# 03-WIFI.net
KiCad netlist of a schematic drawn in Altium Designer
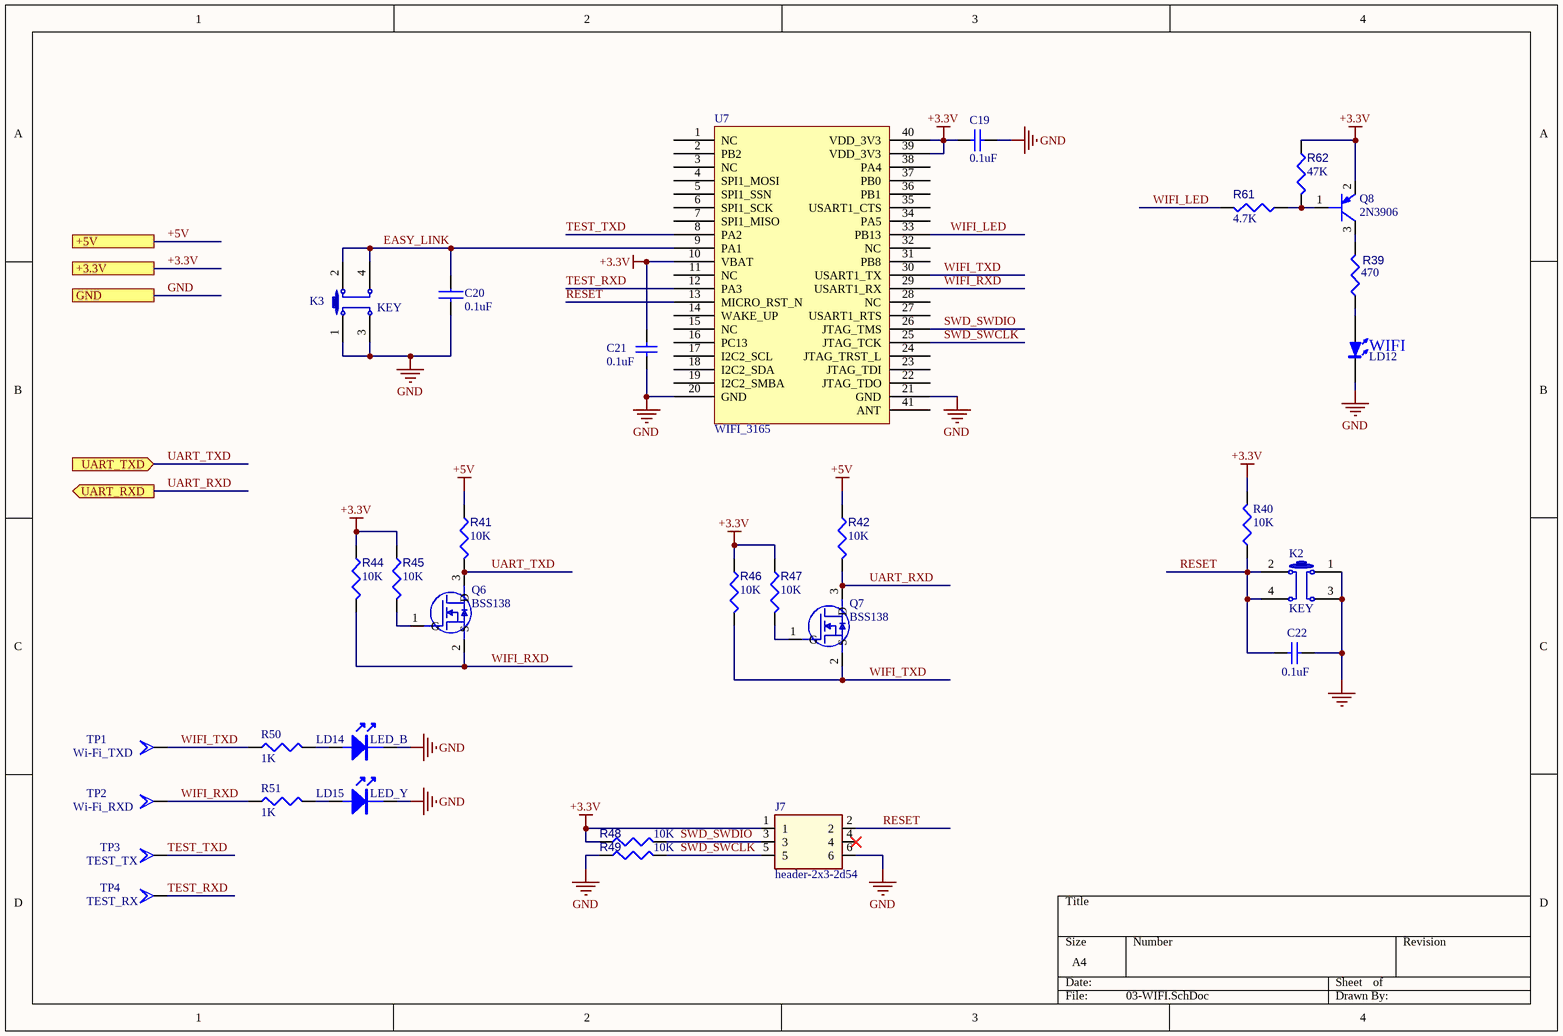
[diagram p0: 03-WIFI.SchDoc]

(export (version "E")
  (design (tool "Eeschema 10.0.6"))
  (components
    (comp (ref "C19")
      (value "0.1uF")
      (footprint "0805_C")
      (description "Capacitor")
      (fields (field (name "PUBLISHER") "Altium Limited"))
      (libsource (lib "EM_SENSOR_V3.01") (part "Cap Semi_1"))
    )
    (comp (ref "C20") (value "0.1uF") (footprint "0805_C") (libsource (lib "EM_SENSOR_V4.1") (part "CAP NP")))
    (comp (ref "C21")
      (value "0.1uF")
      (footprint "0805_C")
      (description "Capacitor")
      (fields (field (name "PUBLISHER") "Altium Limited"))
      (libsource (lib "EM_SENSOR_V2.03") (part "Cap Semi_1"))
    )
    (comp (ref "C22")
      (value "0.1uF")
      (footprint "0805_C")
      (description "Capacitor")
      (fields (field (name "PUBLISHER") "Altium Limited"))
      (libsource (lib "Miscellaneous Devices") (part "Cap"))
    )
    (comp (ref "J7")
      (value "header-2x3-2d54")
      (footprint "HT8550_FLASH_LOADER")
      (libsource (lib "EM_SENSOR_V3.01") (part "header-2x3-2d54"))
    )
    (comp (ref "K2") (value "KEY") (footprint "KEY_SMD5465") (libsource (lib "Schlib1") (part "KEY")))
    (comp (ref "K3") (value "KEY") (footprint "KEY_SMD5465") (libsource (lib "") (part "KEY_1")))
    (comp (ref "LD12")
      (value "WHITE")
      (footprint "LED1")
      (description "LED")
      (libsource (lib "*") (part "LED"))
    )
    (comp (ref "LD14")
      (value "LED_B")
      (footprint "LED_0805")
      (libsource (lib "EM_SENSOR_V2.03") (part "LED"))
    )
    (comp (ref "LD15")
      (value "LED_Y")
      (footprint "LED_0805")
      (libsource (lib "EM_SENSOR_V2.03") (part "LED"))
    )
    (comp (ref "Q6")
      (value "BSS138")
      (footprint "SOT23")
      (description "N-Channel Enhancement MOSFET")
      (libsource (lib "EP_MCB_V6.0") (part "N-Channel Enhancement MOSFET"))
    )
    (comp (ref "Q7")
      (value "BSS138")
      (footprint "SOT23")
      (description "N-Channel Enhancement MOSFET")
      (libsource (lib "EP_MCB_V6.0") (part "N-Channel Enhancement MOSFET"))
    )
    (comp (ref "Q8") (value "2N3906") (footprint "SOT23") (libsource (lib "MySchlib") (part "PNP")))
    (comp (ref "R39")
      (value "470")
      (footprint "0805_R")
      (description "Resistor")
      (fields (field (name "PUBLISHER") "Altium Limited"))
      (libsource (lib "EM_SENSOR_V3.01") (part "Res3"))
    )
    (comp (ref "R40")
      (value "10K")
      (footprint "0805_R")
      (description "Resistor")
      (fields (field (name "PUBLISHER") "Altium Limited"))
      (libsource (lib "Miscellaneous Devices") (part "Res3"))
    )
    (comp (ref "R41")
      (value "10K")
      (footprint "0805_R")
      (description "Resistor")
      (fields (field (name "PUBLISHER") "Altium Limited"))
      (libsource (lib "EP_MCB_V6.0") (part "Res3_3"))
    )
    (comp (ref "R42")
      (value "10K")
      (footprint "0805_R")
      (description "Resistor")
      (fields (field (name "PUBLISHER") "Altium Limited"))
      (libsource (lib "EP_MCB_V6.0") (part "Res3_3"))
    )
    (comp (ref "R44")
      (value "10K")
      (footprint "0805_R")
      (description "Resistor")
      (fields (field (name "PUBLISHER") "Altium Limited"))
      (libsource (lib "EP_MCB_V6.0") (part "Res3_3"))
    )
    (comp (ref "R45")
      (value "10K")
      (footprint "0805_R")
      (description "Resistor")
      (fields (field (name "PUBLISHER") "Altium Limited"))
      (libsource (lib "EP_MCB_V6.0") (part "Res3_3"))
    )
    (comp (ref "R46")
      (value "10K")
      (footprint "0805_R")
      (description "Resistor")
      (fields (field (name "PUBLISHER") "Altium Limited"))
      (libsource (lib "EP_MCB_V6.0") (part "Res3_3"))
    )
    (comp (ref "R47")
      (value "10K")
      (footprint "0805_R")
      (description "Resistor")
      (fields (field (name "PUBLISHER") "Altium Limited"))
      (libsource (lib "EP_MCB_V6.0") (part "Res3_3"))
    )
    (comp (ref "R48")
      (value "10K")
      (footprint "0805_R")
      (description "Resistor")
      (fields (field (name "PUBLISHER") "Altium Limited"))
      (libsource (lib "EM_SENSOR_V3.01") (part "Res3"))
    )
    (comp (ref "R49")
      (value "10K")
      (footprint "0805_R")
      (description "Resistor")
      (fields (field (name "PUBLISHER") "Altium Limited"))
      (libsource (lib "EM_SENSOR_V3.01") (part "Res3"))
    )
    (comp (ref "R50") (value "1K") (footprint "0805_R") (libsource (lib "EM_SENSOR_V2.01") (part "R")))
    (comp (ref "R51") (value "1K") (footprint "0805_R") (libsource (lib "EM_SENSOR_V2.01") (part "R")))
    (comp (ref "R61")
      (value "4.7K")
      (footprint "0805_R")
      (description "Resistor")
      (fields (field (name "PUBLISHER") "Altium Limited"))
      (libsource (lib "EM_SENSOR_V3.01") (part "Res3"))
    )
    (comp (ref "R62")
      (value "47K")
      (footprint "0805_R")
      (description "Resistor")
      (fields (field (name "PUBLISHER") "Altium Limited"))
      (libsource (lib "EM_SENSOR_V3.01") (part "Res3"))
    )
    (comp (ref "TP1")
      (value "Wi-Fi_TXD")
      (footprint "TP_60_30")
      (libsource (lib "EM_SENSOR_V2.01") (part "T POINT A"))
    )
    (comp (ref "TP2")
      (value "Wi-Fi_RXD")
      (footprint "TP_60_30")
      (libsource (lib "EM_SENSOR_V2.01") (part "T POINT A"))
    )
    (comp (ref "TP3")
      (value "TEST_TX")
      (footprint "TP_60_30")
      (libsource (lib "EM_SENSOR_V2.03") (part "T POINT A"))
    )
    (comp (ref "TP4")
      (value "TEST_RX")
      (footprint "TP_60_30")
      (libsource (lib "EM_SENSOR_V2.03") (part "T POINT A"))
    )
    (comp (ref "U7") (value "WIFI_3165") (footprint "EMW3165-P") (libsource (lib "*") (part "WIFI_3165")))
  )
  (nets
    (net (code "1") (name "+3.3V") (class "Default")
      (node (ref "C19") (pin "2") (pinfunction "2_2") (pintype "passive"))
      (node (ref "C21") (pin "2") (pinfunction "2_2") (pintype "passive"))
      (node (ref "J7") (pin "1") (pinfunction "1_1") (pintype "passive"))
      (node (ref "Q8") (pin "2") (pinfunction "EMITTER_2") (pintype "passive"))
      (node (ref "R40") (pin "2") (pinfunction "2_2") (pintype "passive"))
      (node (ref "R44") (pin "1") (pinfunction "1_1") (pintype "passive"))
      (node (ref "R45") (pin "1") (pinfunction "1_1") (pintype "passive"))
      (node (ref "R46") (pin "1") (pinfunction "1_1") (pintype "passive"))
      (node (ref "R47") (pin "1") (pinfunction "1_1") (pintype "passive"))
      (node (ref "R48") (pin "1") (pinfunction "1_1") (pintype "passive"))
      (node (ref "R62") (pin "1") (pinfunction "1_1") (pintype "passive"))
      (node (ref "U7") (pin "10") (pinfunction "VBAT_10") (pintype "passive"))
      (node (ref "U7") (pin "39") (pinfunction "VDD_3V3_39") (pintype "passive"))
      (node (ref "U7") (pin "40") (pinfunction "VDD_3V3_40") (pintype "passive"))
    )
    (net (code "2") (name "+5V") (class "Default")
      (node (ref "R41") (pin "1") (pinfunction "1_1") (pintype "passive"))
      (node (ref "R42") (pin "1") (pinfunction "1_1") (pintype "passive"))
    )
    (net (code "3") (name "/EASY_LINK") (class "Default")
      (node (ref "C20") (pin "1") (pinfunction "1_1") (pintype "passive"))
      (node (ref "K3") (pin "2") (pinfunction "2_2") (pintype "passive"))
      (node (ref "K3") (pin "4") (pinfunction "4_4") (pintype "passive"))
      (node (ref "U7") (pin "9") (pinfunction "PA1_9") (pintype "passive"))
    )
    (net (code "4") (name "/RESET") (class "Default")
      (node (ref "C22") (pin "2") (pinfunction "2_2") (pintype "passive"))
      (node (ref "J7") (pin "2") (pinfunction "2_2") (pintype "passive"))
      (node (ref "K2") (pin "2") (pinfunction "2_2") (pintype "passive"))
      (node (ref "K2") (pin "4") (pinfunction "4_4") (pintype "passive"))
      (node (ref "R40") (pin "1") (pinfunction "1_1") (pintype "passive"))
      (node (ref "U7") (pin "13") (pinfunction "MICRO_RST_N_13") (pintype "passive"))
    )
    (net (code "5") (name "/SWD_SWCLK") (class "Default")
      (node (ref "J7") (pin "5") (pinfunction "5_5") (pintype "passive"))
      (node (ref "R49") (pin "2") (pinfunction "2_2") (pintype "passive"))
      (node (ref "U7") (pin "25") (pinfunction "JTAG_TCK_25") (pintype "passive"))
    )
    (net (code "6") (name "/SWD_SWDIO") (class "Default")
      (node (ref "J7") (pin "3") (pinfunction "3_3") (pintype "passive"))
      (node (ref "R48") (pin "2") (pinfunction "2_2") (pintype "passive"))
      (node (ref "U7") (pin "26") (pinfunction "JTAG_TMS_26") (pintype "passive"))
    )
    (net (code "7") (name "/TEST_RXD") (class "Default")
      (node (ref "TP4") (pin "1") (pinfunction "TP_1") (pintype "passive"))
      (node (ref "U7") (pin "12") (pinfunction "PA3_12") (pintype "passive"))
    )
    (net (code "8") (name "/TEST_TXD") (class "Default")
      (node (ref "TP3") (pin "1") (pinfunction "TP_1") (pintype "passive"))
      (node (ref "U7") (pin "8") (pinfunction "PA2_8") (pintype "passive"))
    )
    (net (code "9") (name "/UART_RXD") (class "Default")
      (node (ref "Q7") (pin "3") (pinfunction "D_3") (pintype "passive"))
      (node (ref "R42") (pin "2") (pinfunction "2_2") (pintype "passive"))
    )
    (net (code "10") (name "/UART_TXD") (class "Default")
      (node (ref "Q6") (pin "3") (pinfunction "D_3") (pintype "passive"))
      (node (ref "R41") (pin "2") (pinfunction "2_2") (pintype "passive"))
    )
    (net (code "11") (name "/WIFI_LED") (class "Default")
      (node (ref "R61") (pin "2") (pinfunction "2_2") (pintype "passive"))
      (node (ref "U7") (pin "33") (pinfunction "PB13_33") (pintype "passive"))
    )
    (net (code "12") (name "/WIFI_RXD") (class "Default")
      (node (ref "Q6") (pin "2") (pinfunction "S_2") (pintype "passive"))
      (node (ref "R44") (pin "2") (pinfunction "2_2") (pintype "passive"))
      (node (ref "R51") (pin "1") (pinfunction "1_1") (pintype "passive"))
      (node (ref "TP2") (pin "1") (pinfunction "TP_1") (pintype "passive"))
      (node (ref "U7") (pin "29") (pinfunction "USART1_RX_29") (pintype "passive"))
    )
    (net (code "13") (name "/WIFI_TXD") (class "Default")
      (node (ref "Q7") (pin "2") (pinfunction "S_2") (pintype "passive"))
      (node (ref "R46") (pin "2") (pinfunction "2_2") (pintype "passive"))
      (node (ref "R50") (pin "1") (pinfunction "1_1") (pintype "passive"))
      (node (ref "TP1") (pin "1") (pinfunction "TP_1") (pintype "passive"))
      (node (ref "U7") (pin "30") (pinfunction "USART1_TX_30") (pintype "passive"))
    )
    (net (code "14") (name "GND") (class "Default")
      (node (ref "C19") (pin "1") (pinfunction "1_1") (pintype "passive"))
      (node (ref "C20") (pin "2") (pinfunction "2_2") (pintype "passive"))
      (node (ref "C21") (pin "1") (pinfunction "1_1") (pintype "passive"))
      (node (ref "C22") (pin "1") (pinfunction "1_1") (pintype "passive"))
      (node (ref "J7") (pin "6") (pinfunction "6_6") (pintype "passive"))
      (node (ref "K2") (pin "1") (pinfunction "1_1") (pintype "passive"))
      (node (ref "K2") (pin "3") (pinfunction "3_3") (pintype "passive"))
      (node (ref "K3") (pin "1") (pinfunction "1_1") (pintype "passive"))
      (node (ref "K3") (pin "3") (pinfunction "3_3") (pintype "passive"))
      (node (ref "LD12") (pin "K") (pinfunction "K_K") (pintype "passive"))
      (node (ref "LD14") (pin "K") (pinfunction "2_K") (pintype "passive"))
      (node (ref "LD15") (pin "K") (pinfunction "2_K") (pintype "passive"))
      (node (ref "R49") (pin "1") (pinfunction "1_1") (pintype "passive"))
      (node (ref "U7") (pin "20") (pinfunction "GND_20") (pintype "passive"))
      (node (ref "U7") (pin "21") (pinfunction "GND_21") (pintype "passive"))
    )
    (net (code "15") (name "Net-(LD12-PadA)") (class "Default")
      (node (ref "LD12") (pin "A") (pinfunction "A_A") (pintype "passive"))
      (node (ref "R39") (pin "1") (pinfunction "1_1") (pintype "passive"))
    )
    (net (code "16") (name "Net-(LD14-1)") (class "Default")
      (node (ref "LD14") (pin "A") (pinfunction "1_A") (pintype "passive"))
      (node (ref "R50") (pin "2") (pinfunction "2_2") (pintype "passive"))
    )
    (net (code "17") (name "Net-(LD15-1)") (class "Default")
      (node (ref "LD15") (pin "A") (pinfunction "1_A") (pintype "passive"))
      (node (ref "R51") (pin "2") (pinfunction "2_2") (pintype "passive"))
    )
    (net (code "18") (name "Net-(Q6-G)") (class "Default")
      (node (ref "Q6") (pin "1") (pinfunction "G_1") (pintype "passive"))
      (node (ref "R45") (pin "2") (pinfunction "2_2") (pintype "passive"))
    )
    (net (code "19") (name "Net-(Q7-G)") (class "Default")
      (node (ref "Q7") (pin "1") (pinfunction "G_1") (pintype "passive"))
      (node (ref "R47") (pin "2") (pinfunction "2_2") (pintype "passive"))
    )
    (net (code "20") (name "Net-(Q8-BASE)") (class "Default")
      (node (ref "Q8") (pin "1") (pinfunction "BASE_1") (pintype "passive"))
      (node (ref "R61") (pin "1") (pinfunction "1_1") (pintype "passive"))
      (node (ref "R62") (pin "2") (pinfunction "2_2") (pintype "passive"))
    )
    (net (code "21") (name "Net-(Q8-COLLECTOR)") (class "Default")
      (node (ref "Q8") (pin "3") (pinfunction "COLLECTOR_3") (pintype "passive"))
      (node (ref "R39") (pin "2") (pinfunction "2_2") (pintype "passive"))
    )
    (net (code "22") (name "unconnected-(J7-Pad4)") (class "Default")
      (node (ref "J7") (pin "4") (pinfunction "4_4") (pintype "passive+no_connect"))
    )
    (net (code "23") (name "unconnected-(U7-ANT-Pad41)") (class "Default")
      (node (ref "U7") (pin "41") (pinfunction "ANT_41") (pintype "passive"))
    )
    (net (code "24") (name "unconnected-(U7-I2C2_SCL-Pad17)") (class "Default")
      (node (ref "U7") (pin "17") (pinfunction "I2C2_SCL_17") (pintype "passive"))
    )
    (net (code "25") (name "unconnected-(U7-I2C2_SDA-Pad18)") (class "Default")
      (node (ref "U7") (pin "18") (pinfunction "I2C2_SDA_18") (pintype "passive"))
    )
    (net (code "26") (name "unconnected-(U7-I2C2_SMBA-Pad19)") (class "Default")
      (node (ref "U7") (pin "19") (pinfunction "I2C2_SMBA_19") (pintype "passive"))
    )
    (net (code "27") (name "unconnected-(U7-JTAG_TDI-Pad23)") (class "Default")
      (node (ref "U7") (pin "23") (pinfunction "JTAG_TDI_23") (pintype "passive"))
    )
    (net (code "28") (name "unconnected-(U7-JTAG_TDO-Pad22)") (class "Default")
      (node (ref "U7") (pin "22") (pinfunction "JTAG_TDO_22") (pintype "passive"))
    )
    (net (code "29") (name "unconnected-(U7-JTAG_TRST_L-Pad24)") (class "Default")
      (node (ref "U7") (pin "24") (pinfunction "JTAG_TRST_L_24") (pintype "passive"))
    )
    (net (code "30") (name "unconnected-(U7-NC-Pad1)") (class "Default")
      (node (ref "U7") (pin "1") (pinfunction "NC_1") (pintype "passive"))
    )
    (net (code "31") (name "unconnected-(U7-NC-Pad3)") (class "Default")
      (node (ref "U7") (pin "3") (pinfunction "NC_3") (pintype "passive"))
    )
    (net (code "32") (name "unconnected-(U7-NC-Pad11)") (class "Default")
      (node (ref "U7") (pin "11") (pinfunction "NC_11") (pintype "passive"))
    )
    (net (code "33") (name "unconnected-(U7-NC-Pad15)") (class "Default")
      (node (ref "U7") (pin "15") (pinfunction "NC_15") (pintype "passive"))
    )
    (net (code "34") (name "unconnected-(U7-NC-Pad28)") (class "Default")
      (node (ref "U7") (pin "28") (pinfunction "NC_28") (pintype "passive"))
    )
    (net (code "35") (name "unconnected-(U7-NC-Pad32)") (class "Default")
      (node (ref "U7") (pin "32") (pinfunction "NC_32") (pintype "passive"))
    )
    (net (code "36") (name "unconnected-(U7-PA4-Pad38)") (class "Default")
      (node (ref "U7") (pin "38") (pinfunction "PA4_38") (pintype "passive"))
    )
    (net (code "37") (name "unconnected-(U7-PA5-Pad34)") (class "Default")
      (node (ref "U7") (pin "34") (pinfunction "PA5_34") (pintype "passive"))
    )
    (net (code "38") (name "unconnected-(U7-PB0-Pad37)") (class "Default")
      (node (ref "U7") (pin "37") (pinfunction "PB0_37") (pintype "passive"))
    )
    (net (code "39") (name "unconnected-(U7-PB1-Pad36)") (class "Default")
      (node (ref "U7") (pin "36") (pinfunction "PB1_36") (pintype "passive"))
    )
    (net (code "40") (name "unconnected-(U7-PB2-Pad2)") (class "Default")
      (node (ref "U7") (pin "2") (pinfunction "PB2_2") (pintype "passive"))
    )
    (net (code "41") (name "unconnected-(U7-PB8-Pad31)") (class "Default")
      (node (ref "U7") (pin "31") (pinfunction "PB8_31") (pintype "passive"))
    )
    (net (code "42") (name "unconnected-(U7-PC13-Pad16)") (class "Default")
      (node (ref "U7") (pin "16") (pinfunction "PC13_16") (pintype "passive"))
    )
    (net (code "43") (name "unconnected-(U7-SPI1_MISO-Pad7)") (class "Default")
      (node (ref "U7") (pin "7") (pinfunction "SPI1_MISO_7") (pintype "passive"))
    )
    (net (code "44") (name "unconnected-(U7-SPI1_MOSI-Pad4)") (class "Default")
      (node (ref "U7") (pin "4") (pinfunction "SPI1_MOSI_4") (pintype "passive"))
    )
    (net (code "45") (name "unconnected-(U7-SPI1_SCK-Pad6)") (class "Default")
      (node (ref "U7") (pin "6") (pinfunction "SPI1_SCK_6") (pintype "passive"))
    )
    (net (code "46") (name "unconnected-(U7-SPI1_SSN-Pad5)") (class "Default")
      (node (ref "U7") (pin "5") (pinfunction "SPI1_SSN_5") (pintype "passive"))
    )
    (net (code "47") (name "unconnected-(U7-USART1_CTS-Pad35)") (class "Default")
      (node (ref "U7") (pin "35") (pinfunction "USART1_CTS_35") (pintype "passive"))
    )
    (net (code "48") (name "unconnected-(U7-USART1_RTS-Pad27)") (class "Default")
      (node (ref "U7") (pin "27") (pinfunction "USART1_RTS_27") (pintype "passive"))
    )
    (net (code "49") (name "unconnected-(U7-WAKE_UP-Pad14)") (class "Default")
      (node (ref "U7") (pin "14") (pinfunction "WAKE_UP_14") (pintype "passive"))
    )
  )
)
